# tiny.net
KiCad netlist of a schematic drawn in EAGLE
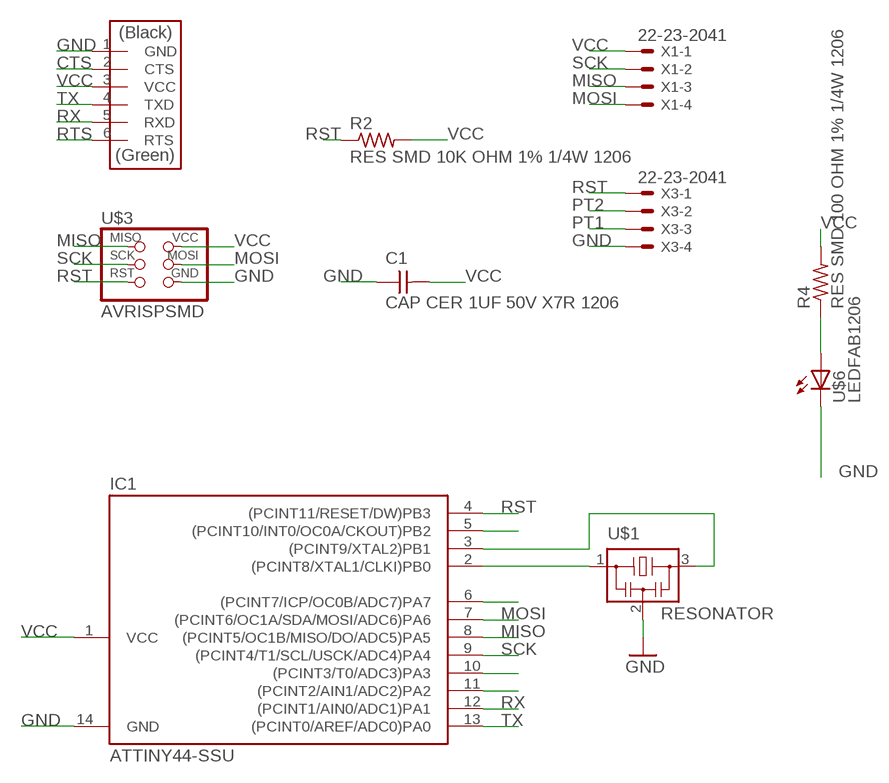
[diagram p0: schematic, sheet 1]

(export (version "E")
  (design (tool "Eeschema 10.0.6"))
  (components
    (comp (ref "C1")
      (value "CAP CER 1UF 50V X7R 1206")
      (footprint "eagle-import:C1206FAB")
      (libsource (lib "eagle-import") (part "CAP-UNPOLARIZEDFAB"))
    )
    (comp (ref "IC1")
      (value "ATTINY44-SSU")
      (footprint "eagle-import:SOIC14")
      (libsource (lib "eagle-import") (part "ATTINY44-SSU"))
    )
    (comp (ref "R2")
      (value "RES SMD 10K OHM 1% 1/4W 1206")
      (footprint "eagle-import:R1206FAB")
      (libsource (lib "eagle-import") (part "RES-US1206FAB"))
    )
    (comp (ref "R4")
      (value "RES SMD 100 OHM 1% 1/4W 1206")
      (footprint "eagle-import:R1206FAB")
      (libsource (lib "eagle-import") (part "RES-US1206FAB"))
    )
    (comp (ref "U$1")
      (value "RESONATOR")
      (footprint "eagle-import:EFOBM")
      (fields (field (name "MF") "Abracon Corporation") (field (name "MPN") "AWSCR-20.00MTD-T"))
      (libsource (lib "eagle-import") (part "RESONATOR"))
    )
    (comp (ref "U$2")
      (value "FTDI-SMD-HEADER")
      (footprint "eagle-import:1X06SMD")
      (libsource (lib "eagle-import") (part "FTDI-SMD-HEADER"))
    )
    (comp (ref "U$3")
      (value "AVRISPSMD")
      (footprint "eagle-import:2X03SMD")
      (libsource (lib "eagle-import") (part "AVRISPSMD"))
    )
    (comp (ref "U$6")
      (value "LEDFAB1206")
      (footprint "eagle-import:LED1206FAB")
      (libsource (lib "eagle-import") (part "LEDFAB1206"))
    )
    (comp (ref "X1")
      (value "22-23-2041")
      (footprint "eagle-import:22-23-2041")
      (fields (field (name "MF") "MOLEX"))
      (libsource (lib "eagle-import") (part "22-23-2041"))
    )
    (comp (ref "X3")
      (value "22-23-2041")
      (footprint "eagle-import:22-23-2041")
      (fields (field (name "MF") "MOLEX"))
      (libsource (lib "eagle-import") (part "22-23-2041"))
    )
  )
  (nets
    (net (code "1") (name "/CTS") (class "Default")
      (node (ref "U$2") (pin "2") (pinfunction "CTS_2") (pintype "bidirectional"))
    )
    (net (code "2") (name "/MISO") (class "Default")
      (node (ref "IC1") (pin "8") (pinfunction "(PCINT5/OC1B/MISO/DO/ADC5)PA5_8") (pintype "bidirectional"))
      (node (ref "U$3") (pin "1") (pinfunction "MISO_1") (pintype "passive"))
      (node (ref "X1") (pin "3") (pinfunction "S_3") (pintype "passive"))
    )
    (net (code "3") (name "/MOSI") (class "Default")
      (node (ref "IC1") (pin "7") (pinfunction "(PCINT6/OC1A/SDA/MOSI/ADC6)PA6_7") (pintype "bidirectional"))
      (node (ref "U$3") (pin "4") (pinfunction "MOSI_4") (pintype "passive"))
      (node (ref "X1") (pin "4") (pinfunction "S_4") (pintype "passive"))
    )
    (net (code "4") (name "/PT1") (class "Default")
      (node (ref "X3") (pin "3") (pinfunction "S_3") (pintype "passive"))
    )
    (net (code "5") (name "/PT2") (class "Default")
      (node (ref "X3") (pin "2") (pinfunction "S_2") (pintype "passive"))
    )
    (net (code "6") (name "/RST") (class "Default")
      (node (ref "IC1") (pin "4") (pinfunction "(PCINT11/RESET/DW)PB3_4") (pintype "bidirectional"))
      (node (ref "R2") (pin "1") (pinfunction "1_1") (pintype "passive"))
      (node (ref "U$3") (pin "5") (pinfunction "RST_5") (pintype "passive"))
      (node (ref "X3") (pin "1") (pinfunction "S_1") (pintype "passive"))
    )
    (net (code "7") (name "/RTS") (class "Default")
      (node (ref "U$2") (pin "6") (pinfunction "RTS_6") (pintype "bidirectional"))
    )
    (net (code "8") (name "/RX") (class "Default")
      (node (ref "IC1") (pin "12") (pinfunction "(PCINT1/AIN0/ADC1)PA1_12") (pintype "bidirectional"))
      (node (ref "U$2") (pin "5") (pinfunction "RXD_5") (pintype "bidirectional"))
    )
    (net (code "9") (name "/SCK") (class "Default")
      (node (ref "IC1") (pin "9") (pinfunction "(PCINT4/T1/SCL/USCK/ADC4)PA4_9") (pintype "bidirectional"))
      (node (ref "U$3") (pin "3") (pinfunction "SCK_3") (pintype "passive"))
      (node (ref "X1") (pin "2") (pinfunction "S_2") (pintype "passive"))
    )
    (net (code "10") (name "/TX") (class "Default")
      (node (ref "IC1") (pin "13") (pinfunction "(PCINT0/AREF/ADC0)PA0_13") (pintype "bidirectional"))
      (node (ref "U$2") (pin "4") (pinfunction "TXD_4") (pintype "bidirectional"))
    )
    (net (code "11") (name "/VCC") (class "Default")
      (node (ref "C1") (pin "2") (pinfunction "2_2") (pintype "passive"))
      (node (ref "IC1") (pin "1") (pinfunction "VCC_1") (pintype "power_in"))
      (node (ref "R2") (pin "2") (pinfunction "2_2") (pintype "passive"))
      (node (ref "R4") (pin "2") (pinfunction "2_2") (pintype "passive"))
      (node (ref "U$2") (pin "3") (pinfunction "VCC_3") (pintype "bidirectional"))
      (node (ref "U$3") (pin "2") (pinfunction "VCC_2") (pintype "passive"))
      (node (ref "X1") (pin "1") (pinfunction "S_1") (pintype "passive"))
    )
    (net (code "12") (name "GND") (class "Default")
      (node (ref "C1") (pin "1") (pinfunction "1_1") (pintype "passive"))
      (node (ref "IC1") (pin "14") (pinfunction "GND_14") (pintype "power_in"))
      (node (ref "U$1") (pin "2") (pinfunction "2_2") (pintype "passive"))
      (node (ref "U$2") (pin "1") (pinfunction "GND_1") (pintype "bidirectional"))
      (node (ref "U$3") (pin "6") (pinfunction "GND_6") (pintype "passive"))
      (node (ref "U$6") (pin "2") (pinfunction "C_2") (pintype "passive"))
      (node (ref "X3") (pin "4") (pinfunction "S_4") (pintype "passive"))
    )
    (net (code "13") (name "Net-(IC1-(PCINT8{slash}XTAL1{slash}CLKI)PB0)") (class "Default")
      (node (ref "IC1") (pin "2") (pinfunction "(PCINT8/XTAL1/CLKI)PB0_2") (pintype "bidirectional"))
      (node (ref "U$1") (pin "1") (pinfunction "1_1") (pintype "passive"))
    )
    (net (code "14") (name "Net-(IC1-(PCINT9{slash}XTAL2)PB1)") (class "Default")
      (node (ref "IC1") (pin "3") (pinfunction "(PCINT9/XTAL2)PB1_3") (pintype "bidirectional"))
      (node (ref "U$1") (pin "3") (pinfunction "3_3") (pintype "passive"))
    )
    (net (code "15") (name "Net-(U$6-A)") (class "Default")
      (node (ref "R4") (pin "1") (pinfunction "1_1") (pintype "passive"))
      (node (ref "U$6") (pin "1") (pinfunction "A_1") (pintype "passive"))
    )
    (net (code "16") (name "unconnected-(IC1-(PCINT2{slash}AIN1{slash}ADC2)PA2-Pad11)") (class "Default")
      (node (ref "IC1") (pin "11") (pinfunction "(PCINT2/AIN1/ADC2)PA2_11") (pintype "bidirectional"))
    )
    (net (code "17") (name "unconnected-(IC1-(PCINT3{slash}T0{slash}ADC3)PA3-Pad10)") (class "Default")
      (node (ref "IC1") (pin "10") (pinfunction "(PCINT3/T0/ADC3)PA3_10") (pintype "bidirectional"))
    )
    (net (code "18") (name "unconnected-(IC1-(PCINT7{slash}ICP{slash}OC0B{slash}ADC7)PA7-Pad6)") (class "Default")
      (node (ref "IC1") (pin "6") (pinfunction "(PCINT7/ICP/OC0B/ADC7)PA7_6") (pintype "bidirectional"))
    )
    (net (code "19") (name "unconnected-(IC1-(PCINT10{slash}INT0{slash}OC0A{slash}CKOUT)PB2-Pad5)") (class "Default")
      (node (ref "IC1") (pin "5") (pinfunction "(PCINT10/INT0/OC0A/CKOUT)PB2_5") (pintype "bidirectional"))
    )
  )
)
